# CS43L22-CNZ_withoutAnalog.net
KiCad netlist of a schematic drawn in EAGLE
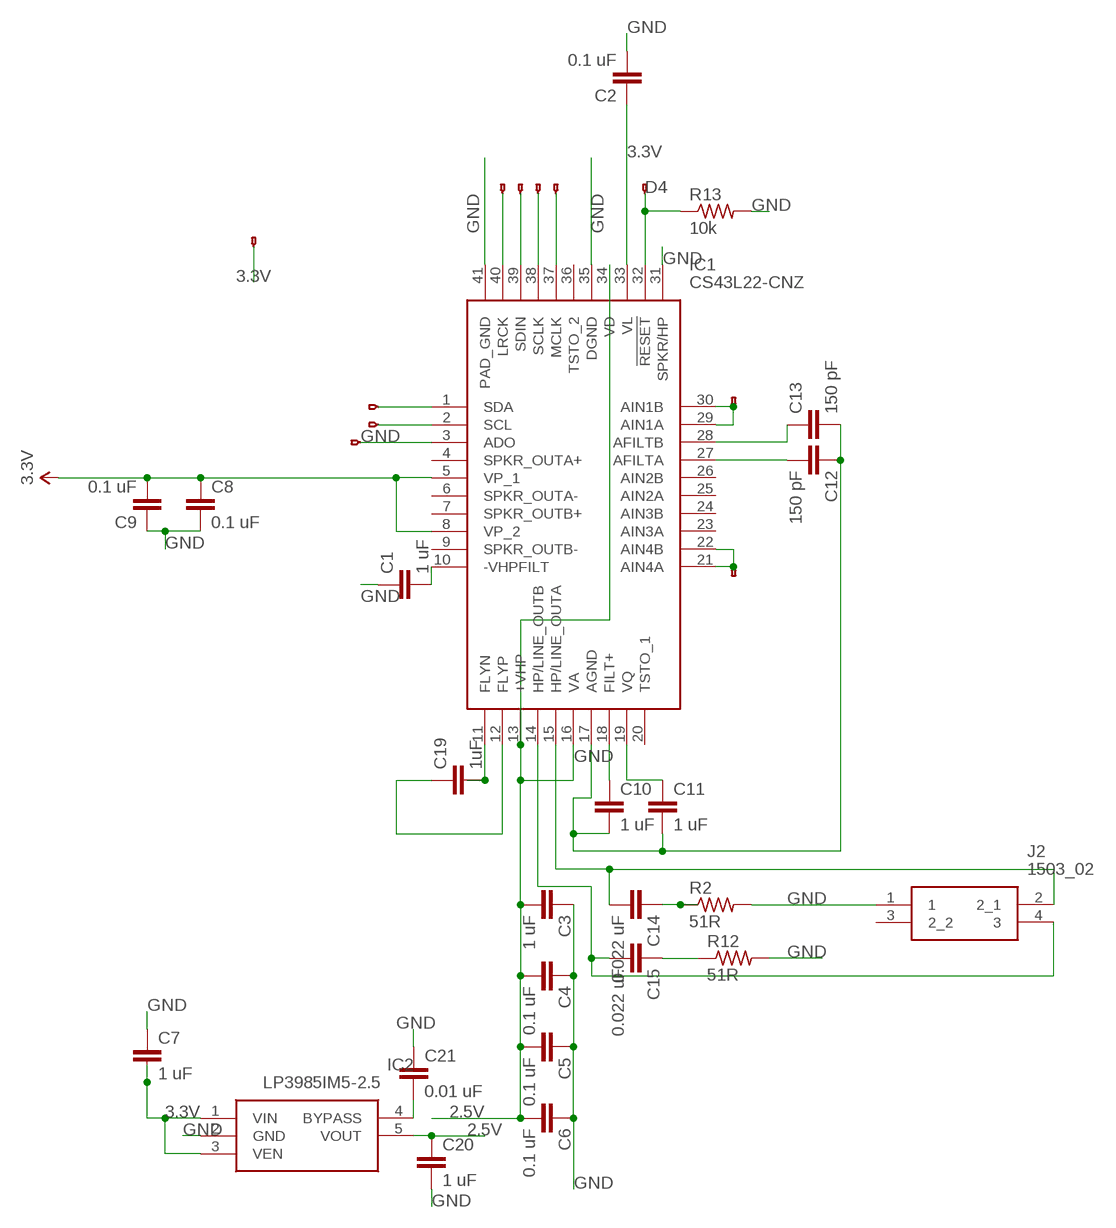
[diagram p0: schematic, sheet 1]

(export (version "E")
  (design (tool "Eeschema 10.0.6"))
  (components
    (comp (ref "C1")
      (value "1 uF")
      (footprint "eagle-import:CAP-PTH-SMALL-KIT")
      (libsource (lib "eagle-import") (part "CAPKIT"))
    )
    (comp (ref "C2")
      (value "0.1 uF")
      (footprint "eagle-import:CAP-PTH-SMALL-KIT")
      (libsource (lib "eagle-import") (part "CAPKIT"))
    )
    (comp (ref "C3")
      (value "1 uF")
      (footprint "eagle-import:CAP-PTH-SMALL-KIT")
      (libsource (lib "eagle-import") (part "CAPKIT"))
    )
    (comp (ref "C4")
      (value "0.1 uF")
      (footprint "eagle-import:CAP-PTH-SMALL-KIT")
      (libsource (lib "eagle-import") (part "CAPKIT"))
    )
    (comp (ref "C5")
      (value "0.1 uF")
      (footprint "eagle-import:CAP-PTH-SMALL-KIT")
      (libsource (lib "eagle-import") (part "CAPKIT"))
    )
    (comp (ref "C6")
      (value "0.1 uF")
      (footprint "eagle-import:CAP-PTH-SMALL-KIT")
      (libsource (lib "eagle-import") (part "CAPKIT"))
    )
    (comp (ref "C7")
      (value "1 uF")
      (footprint "eagle-import:CAP-PTH-SMALL-KIT")
      (libsource (lib "eagle-import") (part "CAPKIT"))
    )
    (comp (ref "C8")
      (value "0.1 uF")
      (footprint "eagle-import:CAP-PTH-SMALL-KIT")
      (libsource (lib "eagle-import") (part "CAPKIT"))
    )
    (comp (ref "C9")
      (value "0.1 uF")
      (footprint "eagle-import:CAP-PTH-SMALL-KIT")
      (libsource (lib "eagle-import") (part "CAPKIT"))
    )
    (comp (ref "C10")
      (value "1 uF")
      (footprint "eagle-import:CAP-PTH-SMALL-KIT")
      (libsource (lib "eagle-import") (part "CAPKIT"))
    )
    (comp (ref "C11")
      (value "1 uF")
      (footprint "eagle-import:CAP-PTH-SMALL-KIT")
      (libsource (lib "eagle-import") (part "CAPKIT"))
    )
    (comp (ref "C12")
      (value "150 pF")
      (footprint "eagle-import:CAP-PTH-SMALL-KIT")
      (libsource (lib "eagle-import") (part "CAPKIT"))
    )
    (comp (ref "C13")
      (value "150 pF")
      (footprint "eagle-import:CAP-PTH-SMALL-KIT")
      (libsource (lib "eagle-import") (part "CAPKIT"))
    )
    (comp (ref "C14")
      (value "0.022 uF")
      (footprint "eagle-import:CAP-PTH-SMALL-KIT")
      (libsource (lib "eagle-import") (part "CAPKIT"))
    )
    (comp (ref "C15")
      (value "0.022 uF")
      (footprint "eagle-import:CAP-PTH-SMALL-KIT")
      (libsource (lib "eagle-import") (part "CAPKIT"))
    )
    (comp (ref "C19")
      (value "1uF")
      (footprint "eagle-import:C2.5-3")
      (libsource (lib "eagle-import") (part "C2,5-3"))
    )
    (comp (ref "C20")
      (value "1 uF")
      (footprint "eagle-import:CAP-PTH-SMALL-KIT")
      (libsource (lib "eagle-import") (part "CAPKIT"))
    )
    (comp (ref "C21")
      (value "0.01 uF")
      (footprint "eagle-import:CAP-PTH-SMALL-KIT")
      (libsource (lib "eagle-import") (part "CAPKIT"))
    )
    (comp (ref "IC1")
      (value "CS43L22-CNZ")
      (footprint "eagle-import:QFN50P600X600X100-41N")
      (fields
        (field (name "MOUSER_PART_NUMBER") "777-CS43L22-CNZ")
        (field (name "RS_PART_NUMBER") "7165851P")
      )
      (libsource (lib "eagle-import") (part "CS43L22-CNZ"))
    )
    (comp (ref "IC2")
      (value "LP3985IM5-2.5")
      (footprint "eagle-import:SOT95P300X120-5N")
      (fields
        (field (name "MOUSER_PART_NUMBER") "926-LP3985IM5-25")
        (field (name "RS_PART_NUMBER") "4433167")
      )
      (libsource (lib "eagle-import") (part "LP3985IM5-2.5"))
    )
    (comp (ref "J2")
      (value "1503_02")
      (footprint "eagle-import:150302")
      (fields (field (name "MANUFACTURER_PART_NUMBER") "1503 02"))
      (libsource (lib "eagle-import") (part "1503_02"))
    )
    (comp (ref "JP1")
      (value "HEADERHOLE-HEADERHOLE")
      (footprint "eagle-import:1X1-HEADER-HOLE")
      (libsource (lib "eagle-import") (part "HEADERHOLE-HEADERHOLE"))
    )
    (comp (ref "JP2")
      (value "HEADERHOLE-HEADERHOLE")
      (footprint "eagle-import:1X1-HEADER-HOLE")
      (libsource (lib "eagle-import") (part "HEADERHOLE-HEADERHOLE"))
    )
    (comp (ref "JP3")
      (value "HEADERHOLE-HEADERHOLE")
      (footprint "eagle-import:1X1-HEADER-HOLE")
      (libsource (lib "eagle-import") (part "HEADERHOLE-HEADERHOLE"))
    )
    (comp (ref "JP4")
      (value "HEADERHOLE-HEADERHOLE")
      (footprint "eagle-import:1X1-HEADER-HOLE")
      (libsource (lib "eagle-import") (part "HEADERHOLE-HEADERHOLE"))
    )
    (comp (ref "JP5")
      (value "HEADERHOLE-HEADERHOLE")
      (footprint "eagle-import:1X1-HEADER-HOLE")
      (libsource (lib "eagle-import") (part "HEADERHOLE-HEADERHOLE"))
    )
    (comp (ref "JP6")
      (value "HEADERHOLE-HEADERHOLE")
      (footprint "eagle-import:1X1-HEADER-HOLE")
      (libsource (lib "eagle-import") (part "HEADERHOLE-HEADERHOLE"))
    )
    (comp (ref "JP7")
      (value "HEADERHOLE-HEADERHOLE")
      (footprint "eagle-import:1X1-HEADER-HOLE")
      (libsource (lib "eagle-import") (part "HEADERHOLE-HEADERHOLE"))
    )
    (comp (ref "JP8")
      (value "HEADERHOLE-HEADERHOLE")
      (footprint "eagle-import:1X1-HEADER-HOLE")
      (libsource (lib "eagle-import") (part "HEADERHOLE-HEADERHOLE"))
    )
    (comp (ref "JP9")
      (value "HEADERHOLE-HEADERHOLE")
      (footprint "eagle-import:1X1-HEADER-HOLE")
      (libsource (lib "eagle-import") (part "HEADERHOLE-HEADERHOLE"))
    )
    (comp (ref "JP18")
      (value "HEADERHOLE-HEADERHOLE")
      (footprint "eagle-import:1X1-HEADER-HOLE")
      (libsource (lib "eagle-import") (part "HEADERHOLE-HEADERHOLE"))
    )
    (comp (ref "JP19")
      (value "HEADERHOLE-HEADERHOLE")
      (footprint "eagle-import:1X1-HEADER-HOLE")
      (libsource (lib "eagle-import") (part "HEADERHOLE-HEADERHOLE"))
    )
    (comp (ref "R2")
      (value "51R")
      (footprint "eagle-import:0204V")
      (libsource (lib "eagle-import") (part "R-US_0204/2V"))
    )
    (comp (ref "R12")
      (value "51R")
      (footprint "eagle-import:0204V")
      (libsource (lib "eagle-import") (part "R-US_0204/2V"))
    )
    (comp (ref "R13")
      (value "10k")
      (footprint "eagle-import:0204V")
      (libsource (lib "eagle-import") (part "R-US_0204/2V"))
    )
  )
  (nets
    (net (code "1") (name "/2.5V") (class "Default")
      (node (ref "C20") (pin "1") (pinfunction "1_1") (pintype "passive"))
      (node (ref "C3") (pin "2") (pinfunction "2_2") (pintype "passive"))
      (node (ref "C4") (pin "2") (pinfunction "2_2") (pintype "passive"))
      (node (ref "C5") (pin "2") (pinfunction "2_2") (pintype "passive"))
      (node (ref "C6") (pin "2") (pinfunction "2_2") (pintype "passive"))
      (node (ref "IC1") (pin "13") (pinfunction "+VHP_13") (pintype "bidirectional"))
      (node (ref "IC1") (pin "16") (pinfunction "VA_16") (pintype "bidirectional"))
      (node (ref "IC1") (pin "34") (pinfunction "VD_34") (pintype "bidirectional"))
      (node (ref "IC2") (pin "5") (pinfunction "VOUT_5") (pintype "bidirectional"))
    )
    (net (code "2") (name "/D4") (class "Default")
      (node (ref "IC1") (pin "32") (pinfunction "~{RESET}_32") (pintype "bidirectional"))
      (node (ref "JP7") (pin "1") (pinfunction "P$1_1") (pintype "bidirectional"))
      (node (ref "R13") (pin "1") (pinfunction "1_1") (pintype "passive"))
    )
    (net (code "3") (name "/GND") (class "Default")
      (node (ref "C1") (pin "1") (pinfunction "1_1") (pintype "passive"))
      (node (ref "C10") (pin "2") (pinfunction "2_2") (pintype "passive"))
      (node (ref "C11") (pin "2") (pinfunction "2_2") (pintype "passive"))
      (node (ref "C12") (pin "1") (pinfunction "1_1") (pintype "passive"))
      (node (ref "C13") (pin "2") (pinfunction "2_2") (pintype "passive"))
      (node (ref "C2") (pin "2") (pinfunction "2_2") (pintype "passive"))
      (node (ref "C20") (pin "2") (pinfunction "2_2") (pintype "passive"))
      (node (ref "C21") (pin "1") (pinfunction "1_1") (pintype "passive"))
      (node (ref "C3") (pin "1") (pinfunction "1_1") (pintype "passive"))
      (node (ref "C4") (pin "1") (pinfunction "1_1") (pintype "passive"))
      (node (ref "C5") (pin "1") (pinfunction "1_1") (pintype "passive"))
      (node (ref "C6") (pin "1") (pinfunction "1_1") (pintype "passive"))
      (node (ref "C7") (pin "1") (pinfunction "1_1") (pintype "passive"))
      (node (ref "C8") (pin "2") (pinfunction "2_2") (pintype "passive"))
      (node (ref "C9") (pin "1") (pinfunction "1_1") (pintype "passive"))
      (node (ref "IC1") (pin "17") (pinfunction "AGND_17") (pintype "bidirectional"))
      (node (ref "IC1") (pin "3") (pinfunction "ADO_3") (pintype "bidirectional"))
      (node (ref "IC1") (pin "31") (pinfunction "SPKR/HP_31") (pintype "bidirectional"))
      (node (ref "IC1") (pin "35") (pinfunction "DGND_35") (pintype "bidirectional"))
      (node (ref "IC1") (pin "41") (pinfunction "PAD_GND_41") (pintype "bidirectional"))
      (node (ref "IC2") (pin "2") (pinfunction "GND_2") (pintype "bidirectional"))
      (node (ref "J2") (pin "1") (pinfunction "1_1") (pintype "bidirectional"))
      (node (ref "JP9") (pin "1") (pinfunction "P$1_1") (pintype "bidirectional"))
      (node (ref "R12") (pin "2") (pinfunction "2_2") (pintype "passive"))
      (node (ref "R13") (pin "2") (pinfunction "2_2") (pintype "passive"))
      (node (ref "R2") (pin "2") (pinfunction "2_2") (pintype "passive"))
    )
    (net (code "4") (name "3.3V") (class "Default")
      (node (ref "C2") (pin "1") (pinfunction "1_1") (pintype "passive"))
      (node (ref "C7") (pin "2") (pinfunction "2_2") (pintype "passive"))
      (node (ref "C8") (pin "1") (pinfunction "1_1") (pintype "passive"))
      (node (ref "C9") (pin "2") (pinfunction "2_2") (pintype "passive"))
      (node (ref "IC1") (pin "33") (pinfunction "VL_33") (pintype "bidirectional"))
      (node (ref "IC1") (pin "5") (pinfunction "VP_1_5") (pintype "bidirectional"))
      (node (ref "IC1") (pin "8") (pinfunction "VP_2_8") (pintype "bidirectional"))
      (node (ref "IC2") (pin "1") (pinfunction "VIN_1") (pintype "bidirectional"))
      (node (ref "IC2") (pin "3") (pinfunction "VEN_3") (pintype "bidirectional"))
      (node (ref "JP8") (pin "1") (pinfunction "P$1_1") (pintype "bidirectional"))
    )
    (net (code "5") (name "Net-(C14-Pad1)") (class "Default")
      (node (ref "C14") (pin "1") (pinfunction "1_1") (pintype "passive"))
      (node (ref "R2") (pin "1") (pinfunction "1_1") (pintype "passive"))
    )
    (net (code "6") (name "Net-(C15-Pad1)") (class "Default")
      (node (ref "C15") (pin "1") (pinfunction "1_1") (pintype "passive"))
      (node (ref "R12") (pin "1") (pinfunction "1_1") (pintype "passive"))
    )
    (net (code "7") (name "Net-(IC1--VHPFILT)") (class "Default")
      (node (ref "C1") (pin "2") (pinfunction "2_2") (pintype "passive"))
      (node (ref "IC1") (pin "10") (pinfunction "-VHPFILT_10") (pintype "bidirectional"))
    )
    (net (code "8") (name "Net-(IC1-AFILTA)") (class "Default")
      (node (ref "C12") (pin "2") (pinfunction "2_2") (pintype "passive"))
      (node (ref "IC1") (pin "27") (pinfunction "AFILTA_27") (pintype "bidirectional"))
    )
    (net (code "9") (name "Net-(IC1-AFILTB)") (class "Default")
      (node (ref "C13") (pin "1") (pinfunction "1_1") (pintype "passive"))
      (node (ref "IC1") (pin "28") (pinfunction "AFILTB_28") (pintype "bidirectional"))
    )
    (net (code "10") (name "Net-(IC1-AIN1A)") (class "Default")
      (node (ref "IC1") (pin "29") (pinfunction "AIN1A_29") (pintype "bidirectional"))
      (node (ref "IC1") (pin "30") (pinfunction "AIN1B_30") (pintype "bidirectional"))
      (node (ref "JP19") (pin "1") (pinfunction "P$1_1") (pintype "bidirectional"))
    )
    (net (code "11") (name "Net-(IC1-AIN4A)") (class "Default")
      (node (ref "IC1") (pin "21") (pinfunction "AIN4A_21") (pintype "bidirectional"))
      (node (ref "IC1") (pin "22") (pinfunction "AIN4B_22") (pintype "bidirectional"))
      (node (ref "JP18") (pin "1") (pinfunction "P$1_1") (pintype "bidirectional"))
    )
    (net (code "12") (name "Net-(IC1-FILT+)") (class "Default")
      (node (ref "C10") (pin "1") (pinfunction "1_1") (pintype "passive"))
      (node (ref "IC1") (pin "18") (pinfunction "FILT+_18") (pintype "bidirectional"))
    )
    (net (code "13") (name "Net-(IC1-FLYN)") (class "Default")
      (node (ref "C19") (pin "2") (pinfunction "2_2") (pintype "passive"))
      (node (ref "IC1") (pin "11") (pinfunction "FLYN_11") (pintype "bidirectional"))
    )
    (net (code "14") (name "Net-(IC1-FLYP)") (class "Default")
      (node (ref "C19") (pin "1") (pinfunction "1_1") (pintype "passive"))
      (node (ref "IC1") (pin "12") (pinfunction "FLYP_12") (pintype "bidirectional"))
    )
    (net (code "15") (name "Net-(IC1-HP{slash}LINE_OUTA)") (class "Default")
      (node (ref "C14") (pin "2") (pinfunction "2_2") (pintype "passive"))
      (node (ref "IC1") (pin "15") (pinfunction "HP/LINE_OUTA_15") (pintype "bidirectional"))
      (node (ref "J2") (pin "2") (pinfunction "2_1_2") (pintype "bidirectional"))
    )
    (net (code "16") (name "Net-(IC1-HP{slash}LINE_OUTB)") (class "Default")
      (node (ref "C15") (pin "2") (pinfunction "2_2") (pintype "passive"))
      (node (ref "IC1") (pin "14") (pinfunction "HP/LINE_OUTB_14") (pintype "bidirectional"))
      (node (ref "J2") (pin "4") (pinfunction "3_4") (pintype "bidirectional"))
    )
    (net (code "17") (name "Net-(IC1-LRCK)") (class "Default")
      (node (ref "IC1") (pin "40") (pinfunction "LRCK_40") (pintype "bidirectional"))
      (node (ref "JP6") (pin "1") (pinfunction "P$1_1") (pintype "bidirectional"))
    )
    (net (code "18") (name "Net-(IC1-MCLK)") (class "Default")
      (node (ref "IC1") (pin "37") (pinfunction "MCLK_37") (pintype "bidirectional"))
      (node (ref "JP3") (pin "1") (pinfunction "P$1_1") (pintype "bidirectional"))
    )
    (net (code "19") (name "Net-(IC1-SCL)") (class "Default")
      (node (ref "IC1") (pin "2") (pinfunction "SCL_2") (pintype "bidirectional"))
      (node (ref "JP2") (pin "1") (pinfunction "P$1_1") (pintype "bidirectional"))
    )
    (net (code "20") (name "Net-(IC1-SCLK)") (class "Default")
      (node (ref "IC1") (pin "38") (pinfunction "SCLK_38") (pintype "bidirectional"))
      (node (ref "JP4") (pin "1") (pinfunction "P$1_1") (pintype "bidirectional"))
    )
    (net (code "21") (name "Net-(IC1-SDA)") (class "Default")
      (node (ref "IC1") (pin "1") (pinfunction "SDA_1") (pintype "bidirectional"))
      (node (ref "JP1") (pin "1") (pinfunction "P$1_1") (pintype "bidirectional"))
    )
    (net (code "22") (name "Net-(IC1-SDIN)") (class "Default")
      (node (ref "IC1") (pin "39") (pinfunction "SDIN_39") (pintype "bidirectional"))
      (node (ref "JP5") (pin "1") (pinfunction "P$1_1") (pintype "bidirectional"))
    )
    (net (code "23") (name "Net-(IC1-VQ)") (class "Default")
      (node (ref "C11") (pin "1") (pinfunction "1_1") (pintype "passive"))
      (node (ref "IC1") (pin "19") (pinfunction "VQ_19") (pintype "bidirectional"))
    )
    (net (code "24") (name "Net-(IC2-BYPASS)") (class "Default")
      (node (ref "C21") (pin "2") (pinfunction "2_2") (pintype "passive"))
      (node (ref "IC2") (pin "4") (pinfunction "BYPASS_4") (pintype "bidirectional"))
    )
    (net (code "25") (name "unconnected-(IC1-AIN2A-Pad25)") (class "Default")
      (node (ref "IC1") (pin "25") (pinfunction "AIN2A_25") (pintype "bidirectional"))
    )
    (net (code "26") (name "unconnected-(IC1-AIN2B-Pad26)") (class "Default")
      (node (ref "IC1") (pin "26") (pinfunction "AIN2B_26") (pintype "bidirectional"))
    )
    (net (code "27") (name "unconnected-(IC1-AIN3A-Pad23)") (class "Default")
      (node (ref "IC1") (pin "23") (pinfunction "AIN3A_23") (pintype "bidirectional"))
    )
    (net (code "28") (name "unconnected-(IC1-AIN3B-Pad24)") (class "Default")
      (node (ref "IC1") (pin "24") (pinfunction "AIN3B_24") (pintype "bidirectional"))
    )
    (net (code "29") (name "unconnected-(IC1-SPKR_OUTA+-Pad4)") (class "Default")
      (node (ref "IC1") (pin "4") (pinfunction "SPKR_OUTA+_4") (pintype "bidirectional"))
    )
    (net (code "30") (name "unconnected-(IC1-SPKR_OUTA--Pad6)") (class "Default")
      (node (ref "IC1") (pin "6") (pinfunction "SPKR_OUTA-_6") (pintype "bidirectional"))
    )
    (net (code "31") (name "unconnected-(IC1-SPKR_OUTB+-Pad7)") (class "Default")
      (node (ref "IC1") (pin "7") (pinfunction "SPKR_OUTB+_7") (pintype "bidirectional"))
    )
    (net (code "32") (name "unconnected-(IC1-SPKR_OUTB--Pad9)") (class "Default")
      (node (ref "IC1") (pin "9") (pinfunction "SPKR_OUTB-_9") (pintype "bidirectional"))
    )
    (net (code "33") (name "unconnected-(IC1-TSTO_1-Pad20)") (class "Default")
      (node (ref "IC1") (pin "20") (pinfunction "TSTO_1_20") (pintype "bidirectional"))
    )
    (net (code "34") (name "unconnected-(IC1-TSTO_2-Pad36)") (class "Default")
      (node (ref "IC1") (pin "36") (pinfunction "TSTO_2_36") (pintype "bidirectional"))
    )
    (net (code "35") (name "unconnected-(J2-2_2-Pad3)") (class "Default")
      (node (ref "J2") (pin "3") (pinfunction "2_2_3") (pintype "bidirectional"))
    )
  )
)
